# mp3412-boost-driver-17mm-mk-1_0.net
KiCad netlist of a schematic drawn in EAGLE
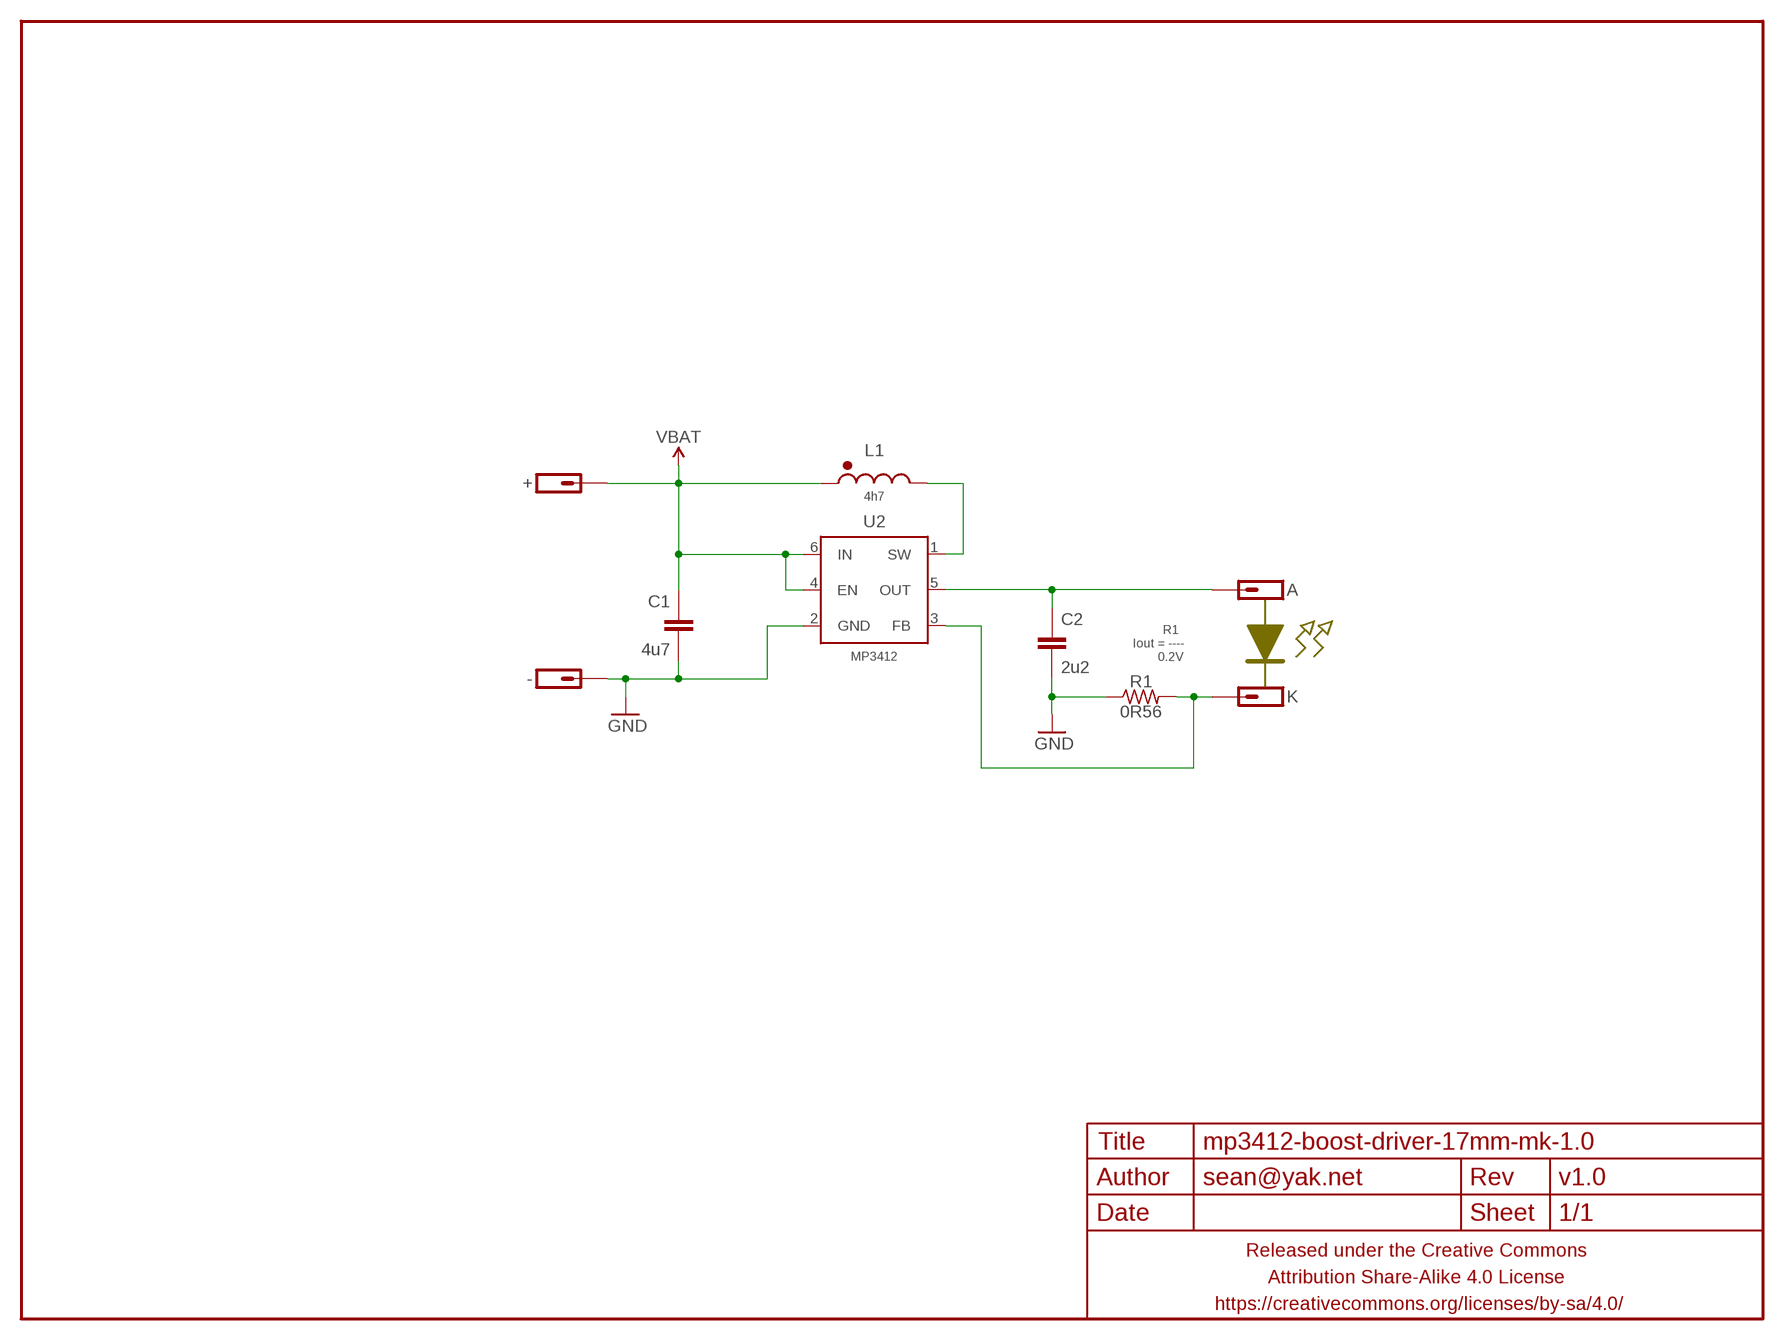
[diagram p0: schematic, sheet 1]

(export (version "E")
  (design (tool "Eeschema 10.0.6"))
  (components
    (comp (ref "+")
      (value "M01NOT-A-VIA-NOPE")
      (footprint "eagle-import:1X01_NOSILK_NOSTOP")
      (libsource (lib "eagle-import") (part "M01NOT-A-VIA-NOPE"))
    )
    (comp (ref "-")
      (value "M01NOT-A-VIA-NOPE")
      (footprint "eagle-import:1X01_NOSILK_NOSTOP")
      (libsource (lib "eagle-import") (part "M01NOT-A-VIA-NOPE"))
    )
    (comp (ref "A")
      (value "M01PTH-1MM-CIR-NS")
      (footprint "eagle-import:1X01-1MM-CIR-NS")
      (libsource (lib "eagle-import") (part "M01PTH-1MM-CIR-NS"))
    )
    (comp (ref "C1")
      (value "4u7")
      (footprint "eagle-import:C0603-TIGHTER")
      (libsource (lib "eagle-import") (part "CAPACITOR-CERAMICC0603-TIGHTER"))
    )
    (comp (ref "C2")
      (value "2u2")
      (footprint "eagle-import:C0603-TIGHTER")
      (libsource (lib "eagle-import") (part "CAPACITOR-CERAMICC0603-TIGHTER"))
    )
    (comp (ref "FRAME1")
      (value "FRAME-LETTERNO_PACKAGE")
      (footprint "eagle-import:DUMMY")
      (fields (field (name "DESIGNER") "sean@yak.net") (field (name "VERSION") "v1.0"))
      (libsource (lib "eagle-import") (part "FRAME-LETTERNO_PACKAGE"))
    )
    (comp (ref "K")
      (value "M01PTH-1MM-CIR-NS")
      (footprint "eagle-import:1X01-1MM-CIR-NS")
      (libsource (lib "eagle-import") (part "M01PTH-1MM-CIR-NS"))
    )
    (comp (ref "L1")
      (value "4h7")
      (footprint "eagle-import:EPL2014")
      (libsource (lib "eagle-import") (part "INDUCTOREPL2014"))
    )
    (comp (ref "R1")
      (value "0R56")
      (footprint "eagle-import:R0603-TIGHTER")
      (libsource (lib "eagle-import") (part "RESISTORR0603-TIGHTER"))
    )
    (comp (ref "U2")
      (value "MP3412")
      (footprint "eagle-import:TSOT-23-6")
      (libsource (lib "eagle-import") (part "MP3412"))
    )
  )
  (nets
    (net (code "1") (name "GND") (class "Default")
      (node (ref "-") (pin "P$1") (pinfunction "1_P$1") (pintype "passive"))
      (node (ref "C1") (pin "2") (pinfunction "2_2") (pintype "passive"))
      (node (ref "C2") (pin "2") (pinfunction "2_2") (pintype "passive"))
      (node (ref "R1") (pin "1") (pinfunction "1_1") (pintype "passive"))
      (node (ref "U2") (pin "2") (pinfunction "GND_2") (pintype "bidirectional"))
    )
    (net (code "2") (name "Net-(L1-2)") (class "Default")
      (node (ref "L1") (pin "P$2") (pinfunction "2_P$2") (pintype "passive"))
      (node (ref "U2") (pin "1") (pinfunction "SW_1") (pintype "bidirectional"))
    )
    (net (code "3") (name "Net-(U2-FB)") (class "Default")
      (node (ref "K") (pin "1") (pinfunction "1_1") (pintype "passive"))
      (node (ref "R1") (pin "2") (pinfunction "2_2") (pintype "passive"))
      (node (ref "U2") (pin "3") (pinfunction "FB_3") (pintype "bidirectional"))
    )
    (net (code "4") (name "Net-(U2-OUT)") (class "Default")
      (node (ref "A") (pin "1") (pinfunction "1_1") (pintype "passive"))
      (node (ref "C2") (pin "1") (pinfunction "1_1") (pintype "passive"))
      (node (ref "U2") (pin "5") (pinfunction "OUT_5") (pintype "bidirectional"))
    )
    (net (code "5") (name "VBAT") (class "Default")
      (node (ref "+") (pin "P$1") (pinfunction "1_P$1") (pintype "passive"))
      (node (ref "C1") (pin "1") (pinfunction "1_1") (pintype "passive"))
      (node (ref "L1") (pin "P$1") (pinfunction "1_P$1") (pintype "passive"))
      (node (ref "U2") (pin "4") (pinfunction "EN_4") (pintype "bidirectional"))
      (node (ref "U2") (pin "6") (pinfunction "IN_6") (pintype "bidirectional"))
    )
  )
)
